# ModemMate.net
KiCad netlist of a schematic drawn in Altium Designer
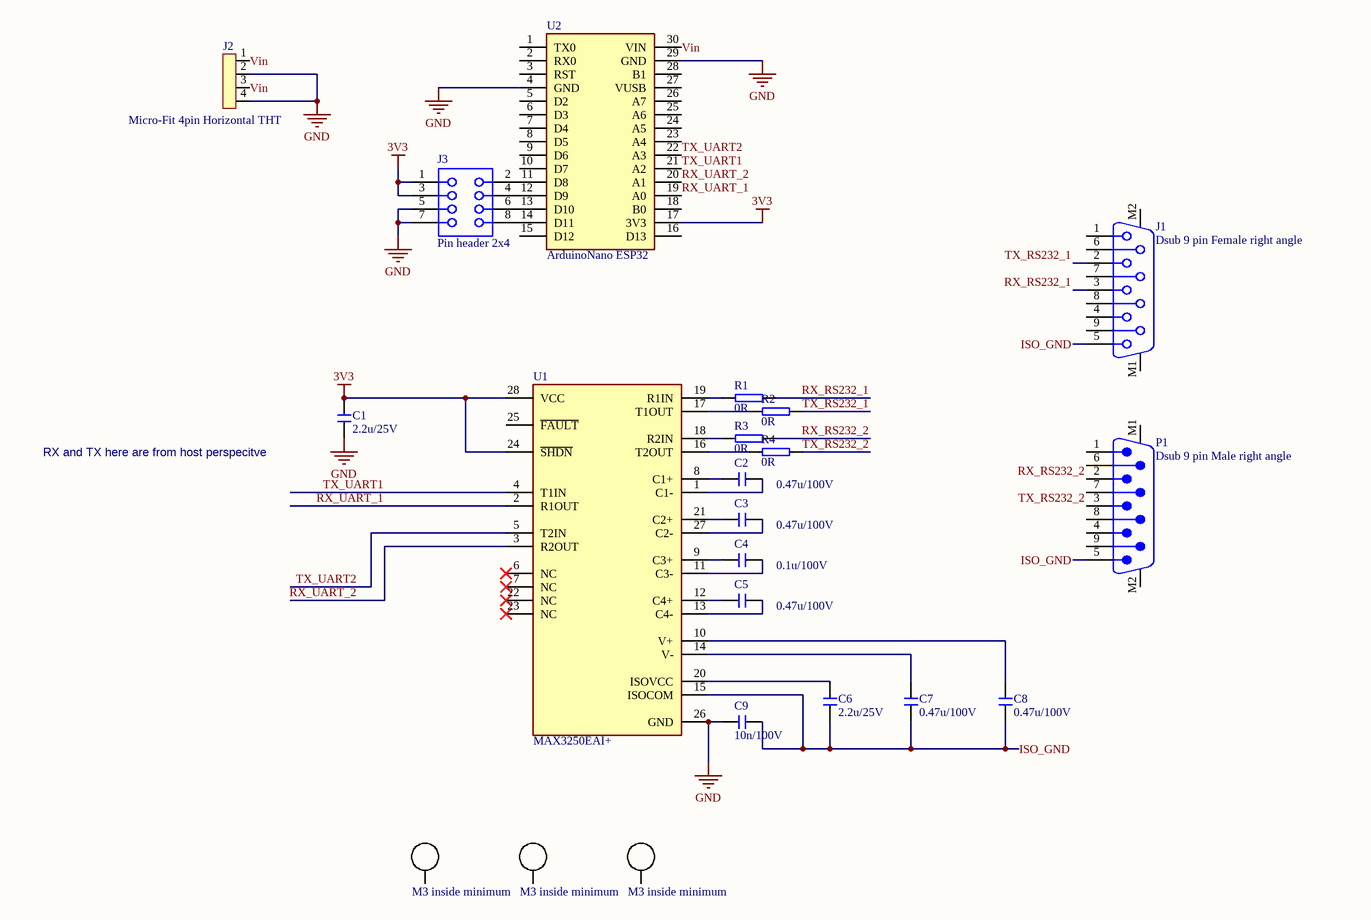
[diagram p0: ModemMate.SchDoc]

(export (version "E")
  (design (tool "Eeschema 10.0.6"))
  (components
    (comp (ref "B1")
      (value "M3 inside minimum")
      (footprint "M3 minimum")
      (description "smaller M3 mounting holde for inside the PCB. should not be used for nuts(tools will not fit)")
      (libsource (lib "Adigo AS") (part "Mounting hole"))
    )
    (comp (ref "B2")
      (value "M3 inside minimum")
      (footprint "M3 minimum")
      (description "smaller M3 mounting holde for inside the PCB. should not be used for nuts(tools will not fit)")
      (libsource (lib "Adigo AS") (part "Mounting hole"))
    )
    (comp (ref "B3")
      (value "M3 inside minimum")
      (footprint "M3 minimum")
      (description "smaller M3 mounting holde for inside the PCB. should not be used for nuts(tools will not fit)")
      (libsource (lib "Adigo AS") (part "Mounting hole"))
    )
    (comp (ref "C1")
      (value "2.2u/25V")
      (footprint "C0805")
      (description "2.2µF, 25V, 0805")
      (fields (field (name "VOLTAGE") "25V") (field (name "TOLERANCE") "10%"))
      (libsource (lib "Adigo AS") (part "Capacitor"))
    )
    (comp (ref "C2")
      (value "0.47u/100V")
      (footprint "C0805")
      (description "0.47uF, 100V, 0805")
      (fields (field (name "VOLTAGE") "100V") (field (name "TOLERANCE") "10%"))
      (libsource (lib "Adigo AS") (part "Capacitor"))
    )
    (comp (ref "C3")
      (value "0.47u/100V")
      (footprint "C0805")
      (description "0.47uF, 100V, 0805")
      (fields (field (name "VOLTAGE") "100V") (field (name "TOLERANCE") "10%"))
      (libsource (lib "Adigo AS") (part "Capacitor"))
    )
    (comp (ref "C4")
      (value "0.1u/100V")
      (footprint "C0603")
      (description "0.1μF, 100V, 0603")
      (fields (field (name "TOLERANCE") "10%") (field (name "VOLTAGE") "100V"))
      (libsource (lib "Adigo AS") (part "Capacitor"))
    )
    (comp (ref "C5")
      (value "0.47u/100V")
      (footprint "C0805")
      (description "0.47uF, 100V, 0805")
      (fields (field (name "VOLTAGE") "100V") (field (name "TOLERANCE") "10%"))
      (libsource (lib "Adigo AS") (part "Capacitor"))
    )
    (comp (ref "C6")
      (value "2.2u/25V")
      (footprint "C0805")
      (description "2.2µF, 25V, 0805")
      (fields (field (name "TOLERANCE") "10%") (field (name "VOLTAGE") "25V"))
      (libsource (lib "Adigo AS") (part "Capacitor"))
    )
    (comp (ref "C7")
      (value "0.47u/100V")
      (footprint "C0805")
      (description "0.47uF, 100V, 0805")
      (fields (field (name "VOLTAGE") "100V") (field (name "TOLERANCE") "10%"))
      (libsource (lib "Adigo AS") (part "Capacitor"))
    )
    (comp (ref "C8")
      (value "0.47u/100V")
      (footprint "C0805")
      (description "0.47uF, 100V, 0805")
      (fields (field (name "VOLTAGE") "100V") (field (name "TOLERANCE") "10%"))
      (libsource (lib "Adigo AS") (part "Capacitor"))
    )
    (comp (ref "C9")
      (value "10n/100V")
      (footprint "C0603")
      (description "10nF, 100V, 0603")
      (fields (field (name "TOLERANCE") "10%") (field (name "VOLTAGE") "100V"))
      (libsource (lib "Adigo AS") (part "Capacitor"))
    )
    (comp (ref "J1")
      (value "Dsub 9 pin Female right angle")
      (footprint "618009231321")
      (description "9 Way Right Angle Through Hole Pcb D-sub Connector Socket, 2.77MM, 2.84MM Pitch")
      (fields (field (name "MANUFACTURER") "Wurth elektronik"))
      (libsource (lib "Adigo AS") (part "D-Sub_Female_09p"))
    )
    (comp (ref "J2")
      (value "Micro-Fit 4pin Horizontal THT")
      (footprint "43045-0400")
      (description "Rectangular Power Connector, 4 Contact(s), Male, Solder Terminal, Plug")
      (fields (field (name "MANUFACTURER") "Molex"))
      (libsource (lib "Adigo AS") (part "Connector, 4pol"))
    )
    (comp (ref "J3")
      (value "Pin header 2x4")
      (footprint "61300821821")
      (fields (field (name "MANUFACTURER") "Wurth Elektronik"))
      (libsource (lib "Adigo AS") (part "Header_Female_2R_08P"))
    )
    (comp (ref "P1")
      (value "Dsub 9 pin Male right angle")
      (footprint "618009231221")
      (description "9 Way Right Angle Through Hole Pcb D-sub Connector Plug, 2.77MM, 2.84MM Pitch")
      (fields (field (name "MANUFACTURER") "Wurth Eletronik"))
      (libsource (lib "Adigo AS") (part "D-Sub_Male_09p"))
    )
    (comp (ref "R1")
      (value "0R")
      (footprint "R0603")
      (description "Resistor 0R, 0603, 1%, SMD")
      (fields (field (name "TOLERANCE") "1%") (field (name "POWER") "100mW"))
      (libsource (lib "Adigo AS") (part "Resistor"))
    )
    (comp (ref "R2")
      (value "0R")
      (footprint "R0603")
      (description "Resistor 0R, 0603, 1%, SMD")
      (fields (field (name "TOLERANCE") "1%") (field (name "POWER") "100mW"))
      (libsource (lib "Adigo AS") (part "Resistor"))
    )
    (comp (ref "R3")
      (value "0R")
      (footprint "R0603")
      (description "Resistor 0R, 0603, 1%, SMD")
      (fields (field (name "TOLERANCE") "1%") (field (name "POWER") "100mW"))
      (libsource (lib "Adigo AS") (part "Resistor"))
    )
    (comp (ref "R4")
      (value "0R")
      (footprint "R0603")
      (description "Resistor 0R, 0603, 1%, SMD")
      (fields (field (name "TOLERANCE") "1%") (field (name "POWER") "100mW"))
      (libsource (lib "Adigo AS") (part "Resistor"))
    )
    (comp (ref "U1")
      (value "MAX3250EAI+")
      (footprint "SSOP-28P, no-thermal")
      (description "isolated Line Transceiver, 2 Func, 2 Driver, 2 Rcvr, BICMOS, PDSO28")
      (fields (field (name "MANUFACTURER") "Maxim"))
      (libsource (lib "Adigo AS") (part "98635781bf7014f5ec0a5fab409c74b"))
    )
    (comp (ref "U2")
      (value "ArduinoNano ESP32")
      (footprint "Copy of New footprint 1")
      (description "Arduino nano development board")
      (fields (field (name "MANUFACTURER") "Arduino"))
      (libsource (lib "Adigo AS") (part "Copy of Arduino Nano"))
    )
  )
  (nets
    (net (code "1") (name "/ISO_GND") (class "Default")
      (node (ref "C6") (pin "2") (pinfunction "2_2") (pintype "passive"))
      (node (ref "C7") (pin "2") (pinfunction "2_2") (pintype "passive"))
      (node (ref "C8") (pin "2") (pinfunction "2_2") (pintype "passive"))
      (node (ref "C9") (pin "1") (pinfunction "1_1") (pintype "passive"))
      (node (ref "J1") (pin "5") (pinfunction "5_5") (pintype "passive"))
      (node (ref "P1") (pin "5") (pinfunction "5_5") (pintype "passive"))
      (node (ref "U1") (pin "15") (pinfunction "ISOCOM_15") (pintype "passive"))
    )
    (net (code "2") (name "/RX_RS232_1") (class "Default")
      (node (ref "J1") (pin "3") (pinfunction "3_3") (pintype "passive"))
      (node (ref "R1") (pin "1") (pinfunction "2_1") (pintype "passive"))
    )
    (net (code "3") (name "/RX_RS232_2") (class "Default")
      (node (ref "P1") (pin "2") (pinfunction "2_2") (pintype "passive"))
      (node (ref "R3") (pin "1") (pinfunction "2_1") (pintype "passive"))
    )
    (net (code "4") (name "/RX_UART_1") (class "Default")
      (node (ref "U1") (pin "2") (pinfunction "R1OUT_2") (pintype "passive"))
      (node (ref "U2") (pin "19") (pinfunction "A0_19") (pintype "passive"))
    )
    (net (code "5") (name "/RX_UART_2") (class "Default")
      (node (ref "U1") (pin "3") (pinfunction "R2OUT_3") (pintype "passive"))
      (node (ref "U2") (pin "20") (pinfunction "A1_20") (pintype "passive"))
    )
    (net (code "6") (name "/TX_RS232_1") (class "Default")
      (node (ref "J1") (pin "2") (pinfunction "2_2") (pintype "passive"))
      (node (ref "R2") (pin "1") (pinfunction "2_1") (pintype "passive"))
    )
    (net (code "7") (name "/TX_RS232_2") (class "Default")
      (node (ref "P1") (pin "3") (pinfunction "3_3") (pintype "passive"))
      (node (ref "R4") (pin "1") (pinfunction "2_1") (pintype "passive"))
    )
    (net (code "8") (name "/TX_UART1") (class "Default")
      (node (ref "U1") (pin "4") (pinfunction "T1IN_4") (pintype "passive"))
      (node (ref "U2") (pin "21") (pinfunction "A2_21") (pintype "passive"))
    )
    (net (code "9") (name "/TX_UART2") (class "Default")
      (node (ref "U1") (pin "5") (pinfunction "T2IN_5") (pintype "passive"))
      (node (ref "U2") (pin "22") (pinfunction "A3_22") (pintype "passive"))
    )
    (net (code "10") (name "/Vin") (class "Default")
      (node (ref "J2") (pin "1") (pinfunction "1_1") (pintype "passive"))
      (node (ref "J2") (pin "3") (pinfunction "3_3") (pintype "passive"))
      (node (ref "U2") (pin "30") (pinfunction "VIN_30") (pintype "passive"))
    )
    (net (code "11") (name "3V3") (class "Default")
      (node (ref "C1") (pin "1") (pinfunction "1_1") (pintype "passive"))
      (node (ref "J3") (pin "1") (pinfunction "1_1") (pintype "passive"))
      (node (ref "J3") (pin "3") (pinfunction "3_3") (pintype "passive"))
      (node (ref "U1") (pin "24") (pinfunction "~{SHDN}_24") (pintype "passive"))
      (node (ref "U1") (pin "28") (pinfunction "VCC_28") (pintype "passive"))
      (node (ref "U2") (pin "17") (pinfunction "3V3_17") (pintype "passive"))
    )
    (net (code "12") (name "GND") (class "Default")
      (node (ref "C1") (pin "2") (pinfunction "2_2") (pintype "passive"))
      (node (ref "C9") (pin "2") (pinfunction "2_2") (pintype "passive"))
      (node (ref "J2") (pin "2") (pinfunction "2_2") (pintype "passive"))
      (node (ref "J2") (pin "4") (pinfunction "4_4") (pintype "passive"))
      (node (ref "J3") (pin "5") (pinfunction "5_5") (pintype "passive"))
      (node (ref "J3") (pin "7") (pinfunction "7_7") (pintype "passive"))
      (node (ref "U1") (pin "26") (pinfunction "GND_26") (pintype "passive"))
      (node (ref "U2") (pin "29") (pinfunction "GND_29") (pintype "passive"))
      (node (ref "U2") (pin "4") (pinfunction "GND_4") (pintype "passive"))
    )
    (net (code "13") (name "Net-(U1-C1+)") (class "Default")
      (node (ref "C2") (pin "1") (pinfunction "1_1") (pintype "passive"))
      (node (ref "U1") (pin "8") (pinfunction "C1+_8") (pintype "passive"))
    )
    (net (code "14") (name "Net-(U1-C1-)") (class "Default")
      (node (ref "C2") (pin "2") (pinfunction "2_2") (pintype "passive"))
      (node (ref "U1") (pin "1") (pinfunction "C1-_1") (pintype "passive"))
    )
    (net (code "15") (name "Net-(U1-C2+)") (class "Default")
      (node (ref "C3") (pin "1") (pinfunction "1_1") (pintype "passive"))
      (node (ref "U1") (pin "21") (pinfunction "C2+_21") (pintype "passive"))
    )
    (net (code "16") (name "Net-(U1-C2-)") (class "Default")
      (node (ref "C3") (pin "2") (pinfunction "2_2") (pintype "passive"))
      (node (ref "U1") (pin "27") (pinfunction "C2-_27") (pintype "passive"))
    )
    (net (code "17") (name "Net-(U1-C3+)") (class "Default")
      (node (ref "C4") (pin "1") (pinfunction "1_1") (pintype "passive"))
      (node (ref "U1") (pin "9") (pinfunction "C3+_9") (pintype "passive"))
    )
    (net (code "18") (name "Net-(U1-C3-)") (class "Default")
      (node (ref "C4") (pin "2") (pinfunction "2_2") (pintype "passive"))
      (node (ref "U1") (pin "11") (pinfunction "C3-_11") (pintype "passive"))
    )
    (net (code "19") (name "Net-(U1-C4+)") (class "Default")
      (node (ref "C5") (pin "1") (pinfunction "1_1") (pintype "passive"))
      (node (ref "U1") (pin "12") (pinfunction "C4+_12") (pintype "passive"))
    )
    (net (code "20") (name "Net-(U1-C4-)") (class "Default")
      (node (ref "C5") (pin "2") (pinfunction "2_2") (pintype "passive"))
      (node (ref "U1") (pin "13") (pinfunction "C4-_13") (pintype "passive"))
    )
    (net (code "21") (name "Net-(U1-ISOVCC)") (class "Default")
      (node (ref "C6") (pin "1") (pinfunction "1_1") (pintype "passive"))
      (node (ref "U1") (pin "20") (pinfunction "ISOVCC_20") (pintype "passive"))
    )
    (net (code "22") (name "Net-(U1-R1IN)") (class "Default")
      (node (ref "R1") (pin "2") (pinfunction "2_2") (pintype "passive"))
      (node (ref "U1") (pin "19") (pinfunction "R1IN_19") (pintype "passive"))
    )
    (net (code "23") (name "Net-(U1-R2IN)") (class "Default")
      (node (ref "R3") (pin "2") (pinfunction "2_2") (pintype "passive"))
      (node (ref "U1") (pin "18") (pinfunction "R2IN_18") (pintype "passive"))
    )
    (net (code "24") (name "Net-(U1-T1OUT)") (class "Default")
      (node (ref "R2") (pin "2") (pinfunction "2_2") (pintype "passive"))
      (node (ref "U1") (pin "17") (pinfunction "T1OUT_17") (pintype "passive"))
    )
    (net (code "25") (name "Net-(U1-T2OUT)") (class "Default")
      (node (ref "R4") (pin "2") (pinfunction "2_2") (pintype "passive"))
      (node (ref "U1") (pin "16") (pinfunction "T2OUT_16") (pintype "passive"))
    )
    (net (code "26") (name "Net-(U1-V+)") (class "Default")
      (node (ref "C8") (pin "1") (pinfunction "1_1") (pintype "passive"))
      (node (ref "U1") (pin "10") (pinfunction "V+_10") (pintype "passive"))
    )
    (net (code "27") (name "Net-(U1-V-)") (class "Default")
      (node (ref "C7") (pin "1") (pinfunction "1_1") (pintype "passive"))
      (node (ref "U1") (pin "14") (pinfunction "V-_14") (pintype "passive"))
    )
    (net (code "28") (name "Net-(U2-D8)") (class "Default")
      (node (ref "J3") (pin "2") (pinfunction "2_2") (pintype "passive"))
      (node (ref "U2") (pin "11") (pinfunction "D8_11") (pintype "passive"))
    )
    (net (code "29") (name "Net-(U2-D9)") (class "Default")
      (node (ref "J3") (pin "4") (pinfunction "4_4") (pintype "passive"))
      (node (ref "U2") (pin "12") (pinfunction "D9_12") (pintype "passive"))
    )
    (net (code "30") (name "Net-(U2-D10)") (class "Default")
      (node (ref "J3") (pin "6") (pinfunction "6_6") (pintype "passive"))
      (node (ref "U2") (pin "13") (pinfunction "D10_13") (pintype "passive"))
    )
    (net (code "31") (name "Net-(U2-D11)") (class "Default")
      (node (ref "J3") (pin "8") (pinfunction "8_8") (pintype "passive"))
      (node (ref "U2") (pin "14") (pinfunction "D11_14") (pintype "passive"))
    )
    (net (code "32") (name "unconnected-(B1-Pad1)") (class "Default")
      (node (ref "B1") (pin "1") (pinfunction "1_1") (pintype "passive"))
    )
    (net (code "33") (name "unconnected-(B2-Pad1)") (class "Default")
      (node (ref "B2") (pin "1") (pinfunction "1_1") (pintype "passive"))
    )
    (net (code "34") (name "unconnected-(B3-Pad1)") (class "Default")
      (node (ref "B3") (pin "1") (pinfunction "1_1") (pintype "passive"))
    )
    (net (code "35") (name "unconnected-(J1-Pad1)") (class "Default")
      (node (ref "J1") (pin "1") (pinfunction "1_1") (pintype "passive"))
    )
    (net (code "36") (name "unconnected-(J1-Pad4)") (class "Default")
      (node (ref "J1") (pin "4") (pinfunction "4_4") (pintype "passive"))
    )
    (net (code "37") (name "unconnected-(J1-Pad6)") (class "Default")
      (node (ref "J1") (pin "6") (pinfunction "6_6") (pintype "passive"))
    )
    (net (code "38") (name "unconnected-(J1-Pad7)") (class "Default")
      (node (ref "J1") (pin "7") (pinfunction "7_7") (pintype "passive"))
    )
    (net (code "39") (name "unconnected-(J1-Pad8)") (class "Default")
      (node (ref "J1") (pin "8") (pinfunction "8_8") (pintype "passive"))
    )
    (net (code "40") (name "unconnected-(J1-Pad9)") (class "Default")
      (node (ref "J1") (pin "9") (pinfunction "9_9") (pintype "passive"))
    )
    (net (code "41") (name "unconnected-(J1-PadM1)") (class "Default")
      (node (ref "J1") (pin "M1") (pinfunction "M1_M1") (pintype "passive"))
    )
    (net (code "42") (name "unconnected-(J1-PadM2)") (class "Default")
      (node (ref "J1") (pin "M2") (pinfunction "M2_M2") (pintype "passive"))
    )
    (net (code "43") (name "unconnected-(P1-Pad1)") (class "Default")
      (node (ref "P1") (pin "1") (pinfunction "1_1") (pintype "passive"))
    )
    (net (code "44") (name "unconnected-(P1-Pad4)") (class "Default")
      (node (ref "P1") (pin "4") (pinfunction "4_4") (pintype "passive"))
    )
    (net (code "45") (name "unconnected-(P1-Pad6)") (class "Default")
      (node (ref "P1") (pin "6") (pinfunction "6_6") (pintype "passive"))
    )
    (net (code "46") (name "unconnected-(P1-Pad7)") (class "Default")
      (node (ref "P1") (pin "7") (pinfunction "7_7") (pintype "passive"))
    )
    (net (code "47") (name "unconnected-(P1-Pad8)") (class "Default")
      (node (ref "P1") (pin "8") (pinfunction "8_8") (pintype "passive"))
    )
    (net (code "48") (name "unconnected-(P1-Pad9)") (class "Default")
      (node (ref "P1") (pin "9") (pinfunction "9_9") (pintype "passive"))
    )
    (net (code "49") (name "unconnected-(P1-PadM1)") (class "Default")
      (node (ref "P1") (pin "M1") (pinfunction "M1_M1") (pintype "passive"))
    )
    (net (code "50") (name "unconnected-(P1-PadM2)") (class "Default")
      (node (ref "P1") (pin "M2") (pinfunction "M2_M2") (pintype "passive"))
    )
    (net (code "51") (name "unconnected-(U1-NC-Pad6)") (class "Default")
      (node (ref "U1") (pin "6") (pinfunction "NC_6") (pintype "passive+no_connect"))
    )
    (net (code "52") (name "unconnected-(U1-NC-Pad7)") (class "Default")
      (node (ref "U1") (pin "7") (pinfunction "NC_7") (pintype "passive+no_connect"))
    )
    (net (code "53") (name "unconnected-(U1-NC-Pad22)") (class "Default")
      (node (ref "U1") (pin "22") (pinfunction "NC_22") (pintype "passive+no_connect"))
    )
    (net (code "54") (name "unconnected-(U1-NC-Pad23)") (class "Default")
      (node (ref "U1") (pin "23") (pinfunction "NC_23") (pintype "passive+no_connect"))
    )
    (net (code "55") (name "unconnected-(U1-~{FAULT}-Pad25)") (class "Default")
      (node (ref "U1") (pin "25") (pinfunction "~{FAULT}_25") (pintype "passive"))
    )
    (net (code "56") (name "unconnected-(U2-A4-Pad23)") (class "Default")
      (node (ref "U2") (pin "23") (pinfunction "A4_23") (pintype "passive"))
    )
    (net (code "57") (name "unconnected-(U2-A5-Pad24)") (class "Default")
      (node (ref "U2") (pin "24") (pinfunction "A5_24") (pintype "passive"))
    )
    (net (code "58") (name "unconnected-(U2-A6-Pad25)") (class "Default")
      (node (ref "U2") (pin "25") (pinfunction "A6_25") (pintype "passive"))
    )
    (net (code "59") (name "unconnected-(U2-A7-Pad26)") (class "Default")
      (node (ref "U2") (pin "26") (pinfunction "A7_26") (pintype "passive"))
    )
    (net (code "60") (name "unconnected-(U2-B0-Pad18)") (class "Default")
      (node (ref "U2") (pin "18") (pinfunction "B0_18") (pintype "passive"))
    )
    (net (code "61") (name "unconnected-(U2-B1-Pad28)") (class "Default")
      (node (ref "U2") (pin "28") (pinfunction "B1_28") (pintype "passive"))
    )
    (net (code "62") (name "unconnected-(U2-D2-Pad5)") (class "Default")
      (node (ref "U2") (pin "5") (pinfunction "D2_5") (pintype "passive"))
    )
    (net (code "63") (name "unconnected-(U2-D3-Pad6)") (class "Default")
      (node (ref "U2") (pin "6") (pinfunction "D3_6") (pintype "passive"))
    )
    (net (code "64") (name "unconnected-(U2-D4-Pad7)") (class "Default")
      (node (ref "U2") (pin "7") (pinfunction "D4_7") (pintype "passive"))
    )
    (net (code "65") (name "unconnected-(U2-D5-Pad8)") (class "Default")
      (node (ref "U2") (pin "8") (pinfunction "D5_8") (pintype "passive"))
    )
    (net (code "66") (name "unconnected-(U2-D6-Pad9)") (class "Default")
      (node (ref "U2") (pin "9") (pinfunction "D6_9") (pintype "passive"))
    )
    (net (code "67") (name "unconnected-(U2-D7-Pad10)") (class "Default")
      (node (ref "U2") (pin "10") (pinfunction "D7_10") (pintype "passive"))
    )
    (net (code "68") (name "unconnected-(U2-D12-Pad15)") (class "Default")
      (node (ref "U2") (pin "15") (pinfunction "D12_15") (pintype "passive"))
    )
    (net (code "69") (name "unconnected-(U2-D13-Pad16)") (class "Default")
      (node (ref "U2") (pin "16") (pinfunction "D13_16") (pintype "passive"))
    )
    (net (code "70") (name "unconnected-(U2-RST-Pad3)") (class "Default")
      (node (ref "U2") (pin "3") (pinfunction "RST_3") (pintype "passive"))
    )
    (net (code "71") (name "unconnected-(U2-RX0-Pad2)") (class "Default")
      (node (ref "U2") (pin "2") (pinfunction "RX0_2") (pintype "passive"))
    )
    (net (code "72") (name "unconnected-(U2-TX0-Pad1)") (class "Default")
      (node (ref "U2") (pin "1") (pinfunction "TX0_1") (pintype "passive"))
    )
    (net (code "73") (name "unconnected-(U2-VUSB-Pad27)") (class "Default")
      (node (ref "U2") (pin "27") (pinfunction "VUSB_27") (pintype "passive"))
    )
  )
)
